# SuperPNP.net
KiCad netlist of a schematic drawn in EAGLE
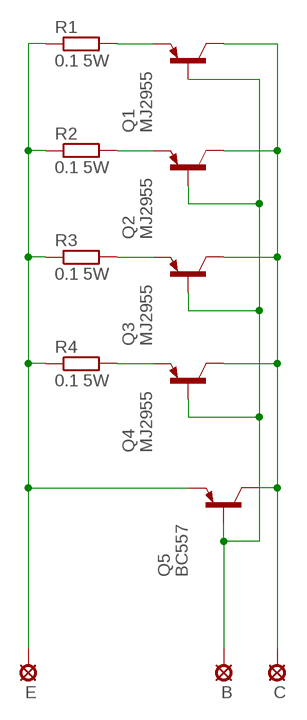
[diagram p0: schematic, sheet 1]

(export (version "E")
  (design (tool "Eeschema 10.0.6"))
  (components
    (comp (ref "B")
      (value "SE14")
      (footprint "eagle-import:SE14")
      (libsource (lib "eagle-import") (part "SE14"))
    )
    (comp (ref "C")
      (value "SE14")
      (footprint "eagle-import:SE14")
      (libsource (lib "eagle-import") (part "SE14"))
    )
    (comp (ref "E")
      (value "SE14")
      (footprint "eagle-import:SE14")
      (libsource (lib "eagle-import") (part "SE14"))
    )
    (comp (ref "Q1")
      (value "MJ2955")
      (footprint "eagle-import:TO3")
      (libsource (lib "eagle-import") (part "MJ2955"))
    )
    (comp (ref "Q2")
      (value "MJ2955")
      (footprint "eagle-import:TO3")
      (libsource (lib "eagle-import") (part "MJ2955"))
    )
    (comp (ref "Q3")
      (value "MJ2955")
      (footprint "eagle-import:TO3")
      (libsource (lib "eagle-import") (part "MJ2955"))
    )
    (comp (ref "Q4")
      (value "MJ2955")
      (footprint "eagle-import:TO3")
      (libsource (lib "eagle-import") (part "MJ2955"))
    )
    (comp (ref "Q5")
      (value "BC557")
      (footprint "eagle-import:TO92")
      (libsource (lib "eagle-import") (part "BC557"))
    )
    (comp (ref "R1")
      (value "0.1 5W")
      (footprint "eagle-import:0617_22")
      (libsource (lib "eagle-import") (part "R-EU_0617/22"))
    )
    (comp (ref "R2")
      (value "0.1 5W")
      (footprint "eagle-import:0617_22")
      (libsource (lib "eagle-import") (part "R-EU_0617/22"))
    )
    (comp (ref "R3")
      (value "0.1 5W")
      (footprint "eagle-import:0617_22")
      (libsource (lib "eagle-import") (part "R-EU_0617/22"))
    )
    (comp (ref "R4")
      (value "0.1 5W")
      (footprint "eagle-import:0617_22")
      (libsource (lib "eagle-import") (part "R-EU_0617/22"))
    )
  )
  (nets
    (net (code "1") (name "Net-(Q1-PadE)") (class "Default")
      (node (ref "Q1") (pin "E") (pinfunction "E_E") (pintype "passive"))
      (node (ref "R1") (pin "2") (pinfunction "2_2") (pintype "passive"))
    )
    (net (code "2") (name "Net-(Q2-PadE)") (class "Default")
      (node (ref "Q2") (pin "E") (pinfunction "E_E") (pintype "passive"))
      (node (ref "R2") (pin "2") (pinfunction "2_2") (pintype "passive"))
    )
    (net (code "3") (name "Net-(Q3-PadE)") (class "Default")
      (node (ref "Q3") (pin "E") (pinfunction "E_E") (pintype "passive"))
      (node (ref "R3") (pin "2") (pinfunction "2_2") (pintype "passive"))
    )
    (net (code "4") (name "Net-(Q4-PadE)") (class "Default")
      (node (ref "Q4") (pin "E") (pinfunction "E_E") (pintype "passive"))
      (node (ref "R4") (pin "2") (pinfunction "2_2") (pintype "passive"))
    )
    (net (code "5") (name "Net-(Q5-B)") (class "Default")
      (node (ref "B") (pin "MP") (pinfunction "MP_MP") (pintype "passive"))
      (node (ref "Q1") (pin "B") (pinfunction "B_B") (pintype "passive"))
      (node (ref "Q2") (pin "B") (pinfunction "B_B") (pintype "passive"))
      (node (ref "Q3") (pin "B") (pinfunction "B_B") (pintype "passive"))
      (node (ref "Q4") (pin "B") (pinfunction "B_B") (pintype "passive"))
      (node (ref "Q5") (pin "2") (pinfunction "B_2") (pintype "passive"))
    )
    (net (code "6") (name "Net-(Q5-C)") (class "Default")
      (node (ref "C") (pin "MP") (pinfunction "MP_MP") (pintype "passive"))
      (node (ref "Q1") (pin "C") (pinfunction "C_C") (pintype "passive"))
      (node (ref "Q1") (pin "C/") (pinfunction "C_C/") (pintype "passive"))
      (node (ref "Q2") (pin "C") (pinfunction "C_C") (pintype "passive"))
      (node (ref "Q2") (pin "C/") (pinfunction "C_C/") (pintype "passive"))
      (node (ref "Q3") (pin "C") (pinfunction "C_C") (pintype "passive"))
      (node (ref "Q3") (pin "C/") (pinfunction "C_C/") (pintype "passive"))
      (node (ref "Q4") (pin "C") (pinfunction "C_C") (pintype "passive"))
      (node (ref "Q4") (pin "C/") (pinfunction "C_C/") (pintype "passive"))
      (node (ref "Q5") (pin "3") (pinfunction "C_3") (pintype "passive"))
    )
    (net (code "7") (name "Net-(Q5-E)") (class "Default")
      (node (ref "E") (pin "MP") (pinfunction "MP_MP") (pintype "passive"))
      (node (ref "Q5") (pin "1") (pinfunction "E_1") (pintype "passive"))
      (node (ref "R1") (pin "1") (pinfunction "1_1") (pintype "passive"))
      (node (ref "R2") (pin "1") (pinfunction "1_1") (pintype "passive"))
      (node (ref "R3") (pin "1") (pinfunction "1_1") (pintype "passive"))
      (node (ref "R4") (pin "1") (pinfunction "1_1") (pintype "passive"))
    )
  )
)
